# con-bot-j2-1.net
KiCad netlist of a schematic drawn in Altium Designer
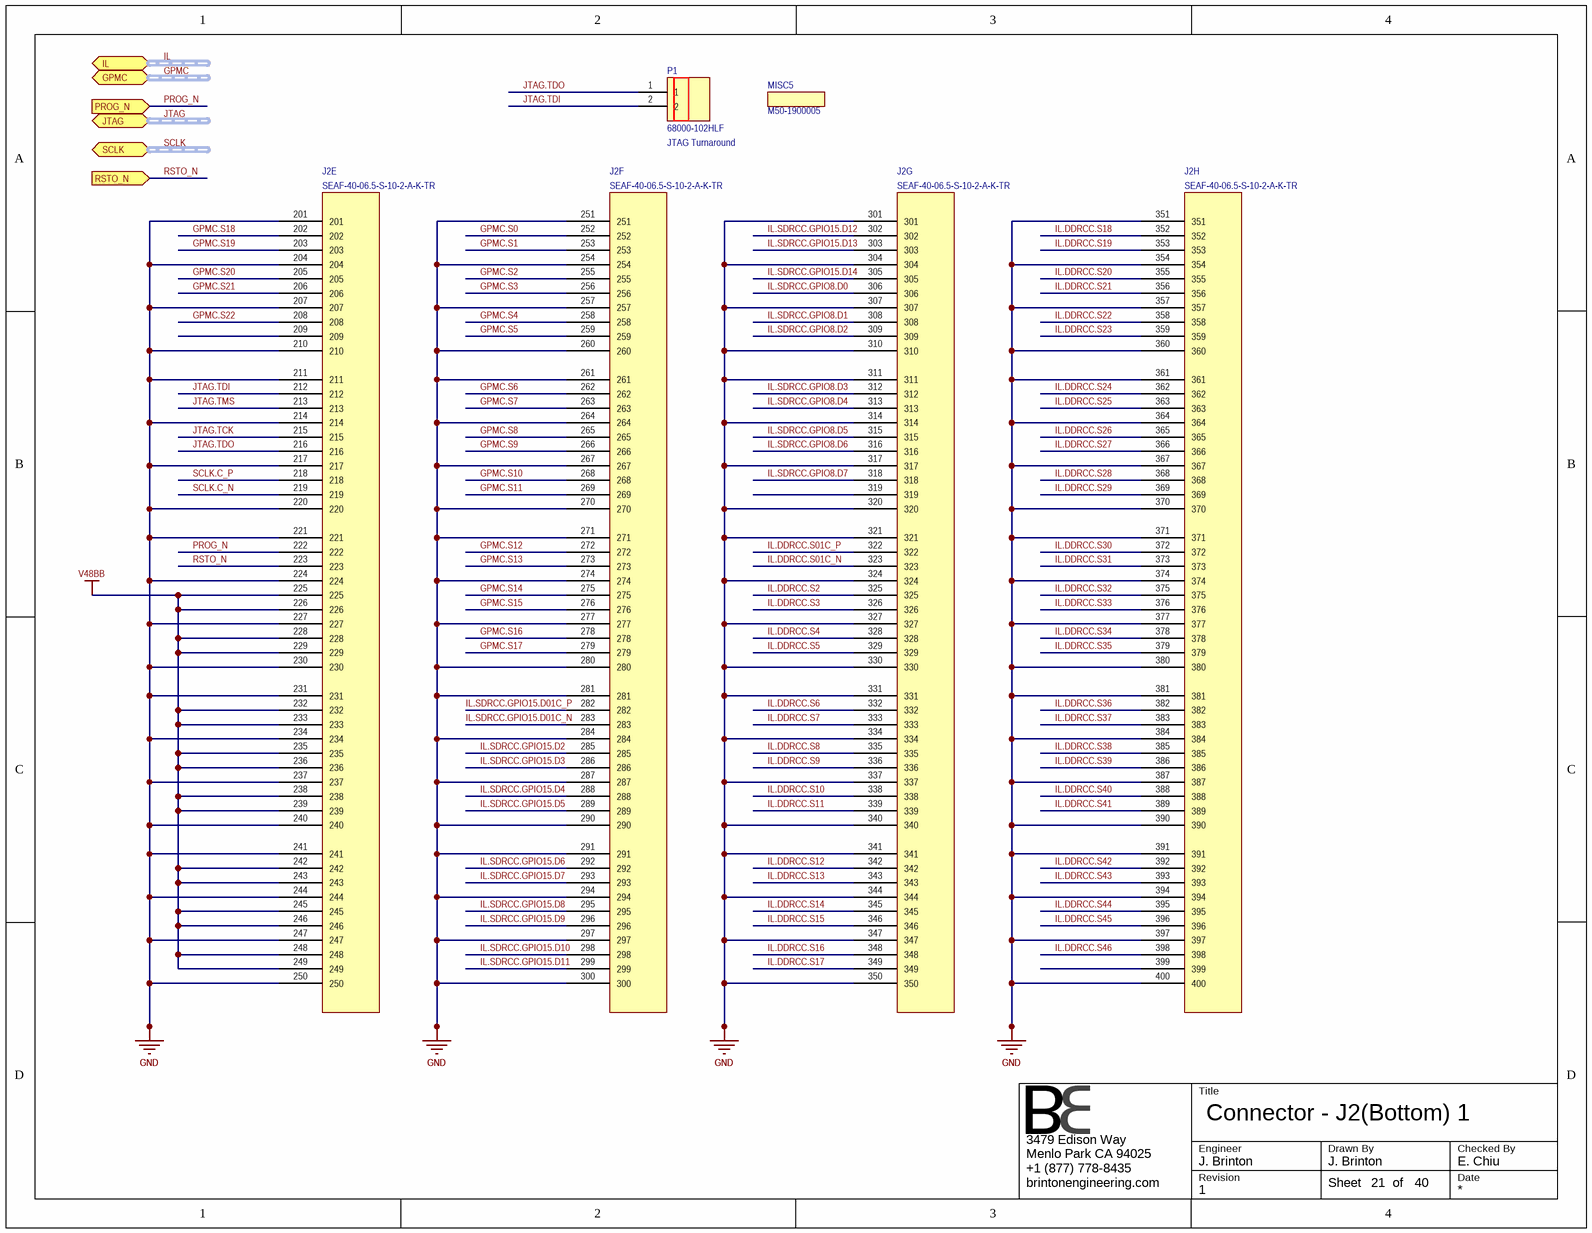
[diagram p0: con-bot-j2-1.SchDoc]

(export (version "E")
  (design (tool "Eeschema 10.0.6"))
  (components
    (comp (ref "J2")
      (value "SEAF-40-06.5-S-10-2-A-K-TR")
      (footprint "samtec:SEAF-40-06.5-S-10-2-A-K-TR")
      (description "Terminal Array Assembly, Surface Mount, 0.050\" Pitch, 400 Pins")
      (fields (field (name "MANUFACTURER") "Samtec"))
      (libsource (lib "samtec") (part "SEAF-40-06.5-S-10-2-A-K-TR"))
    )
    (comp (ref "MISC5")
      (value "M50-1900005")
      (description "1.27mm Jumper Socket")
      (fields (field (name "MANUFACTURER") "Harwin"))
      (libsource (lib "harwin") (part "M50-1900005"))
    )
    (comp (ref "P1")
      (value "68000-102HLF")
      (footprint "68000-102HLF")
      (description "Connector; Header; 2 Position; 0.1\" Pitch")
      (fields (field (name "MANUFACTURER") "FCI"))
      (libsource (lib "fci") (part "68000-102HLF"))
    )
  )
  (nets
    (net (code "5") (name "/GPMC.S0") (class "Default")
      (node (ref "J2") (pin "252") (pinfunction "252_252") (pintype "passive"))
    )
    (net (code "6") (name "/GPMC.S1") (class "Default")
      (node (ref "J2") (pin "253") (pinfunction "253_253") (pintype "passive"))
    )
    (net (code "7") (name "/GPMC.S2") (class "Default")
      (node (ref "J2") (pin "255") (pinfunction "255_255") (pintype "passive"))
    )
    (net (code "8") (name "/GPMC.S3") (class "Default")
      (node (ref "J2") (pin "256") (pinfunction "256_256") (pintype "passive"))
    )
    (net (code "9") (name "/GPMC.S4") (class "Default")
      (node (ref "J2") (pin "258") (pinfunction "258_258") (pintype "passive"))
    )
    (net (code "10") (name "/GPMC.S5") (class "Default")
      (node (ref "J2") (pin "259") (pinfunction "259_259") (pintype "passive"))
    )
    (net (code "11") (name "/GPMC.S6") (class "Default")
      (node (ref "J2") (pin "262") (pinfunction "262_262") (pintype "passive"))
    )
    (net (code "12") (name "/GPMC.S7") (class "Default")
      (node (ref "J2") (pin "263") (pinfunction "263_263") (pintype "passive"))
    )
    (net (code "13") (name "/GPMC.S8") (class "Default")
      (node (ref "J2") (pin "265") (pinfunction "265_265") (pintype "passive"))
    )
    (net (code "14") (name "/GPMC.S9") (class "Default")
      (node (ref "J2") (pin "266") (pinfunction "266_266") (pintype "passive"))
    )
    (net (code "15") (name "/GPMC.S10") (class "Default")
      (node (ref "J2") (pin "268") (pinfunction "268_268") (pintype "passive"))
    )
    (net (code "16") (name "/GPMC.S11") (class "Default")
      (node (ref "J2") (pin "269") (pinfunction "269_269") (pintype "passive"))
    )
    (net (code "17") (name "/GPMC.S12") (class "Default")
      (node (ref "J2") (pin "272") (pinfunction "272_272") (pintype "passive"))
    )
    (net (code "18") (name "/GPMC.S13") (class "Default")
      (node (ref "J2") (pin "273") (pinfunction "273_273") (pintype "passive"))
    )
    (net (code "19") (name "/GPMC.S14") (class "Default")
      (node (ref "J2") (pin "275") (pinfunction "275_275") (pintype "passive"))
    )
    (net (code "20") (name "/GPMC.S15") (class "Default")
      (node (ref "J2") (pin "276") (pinfunction "276_276") (pintype "passive"))
    )
    (net (code "21") (name "/GPMC.S16") (class "Default")
      (node (ref "J2") (pin "278") (pinfunction "278_278") (pintype "passive"))
    )
    (net (code "22") (name "/GPMC.S17") (class "Default")
      (node (ref "J2") (pin "279") (pinfunction "279_279") (pintype "passive"))
    )
    (net (code "23") (name "/GPMC.S18") (class "Default")
      (node (ref "J2") (pin "202") (pinfunction "202_202") (pintype "passive"))
    )
    (net (code "24") (name "/GPMC.S19") (class "Default")
      (node (ref "J2") (pin "203") (pinfunction "203_203") (pintype "passive"))
    )
    (net (code "25") (name "/GPMC.S20") (class "Default")
      (node (ref "J2") (pin "205") (pinfunction "205_205") (pintype "passive"))
    )
    (net (code "26") (name "/GPMC.S21") (class "Default")
      (node (ref "J2") (pin "206") (pinfunction "206_206") (pintype "passive"))
    )
    (net (code "27") (name "/GPMC.S22") (class "Default")
      (node (ref "J2") (pin "208") (pinfunction "208_208") (pintype "passive"))
    )
    (net (code "28") (name "/IL.DDRCC.S01C_N") (class "Default")
      (node (ref "J2") (pin "323") (pinfunction "323_323") (pintype "passive"))
    )
    (net (code "29") (name "/IL.DDRCC.S01C_P") (class "Default")
      (node (ref "J2") (pin "322") (pinfunction "322_322") (pintype "passive"))
    )
    (net (code "30") (name "/IL.DDRCC.S2") (class "Default")
      (node (ref "J2") (pin "325") (pinfunction "325_325") (pintype "passive"))
    )
    (net (code "31") (name "/IL.DDRCC.S3") (class "Default")
      (node (ref "J2") (pin "326") (pinfunction "326_326") (pintype "passive"))
    )
    (net (code "32") (name "/IL.DDRCC.S4") (class "Default")
      (node (ref "J2") (pin "328") (pinfunction "328_328") (pintype "passive"))
    )
    (net (code "33") (name "/IL.DDRCC.S5") (class "Default")
      (node (ref "J2") (pin "329") (pinfunction "329_329") (pintype "passive"))
    )
    (net (code "34") (name "/IL.DDRCC.S6") (class "Default")
      (node (ref "J2") (pin "332") (pinfunction "332_332") (pintype "passive"))
    )
    (net (code "35") (name "/IL.DDRCC.S7") (class "Default")
      (node (ref "J2") (pin "333") (pinfunction "333_333") (pintype "passive"))
    )
    (net (code "36") (name "/IL.DDRCC.S8") (class "Default")
      (node (ref "J2") (pin "335") (pinfunction "335_335") (pintype "passive"))
    )
    (net (code "37") (name "/IL.DDRCC.S9") (class "Default")
      (node (ref "J2") (pin "336") (pinfunction "336_336") (pintype "passive"))
    )
    (net (code "38") (name "/IL.DDRCC.S10") (class "Default")
      (node (ref "J2") (pin "338") (pinfunction "338_338") (pintype "passive"))
    )
    (net (code "39") (name "/IL.DDRCC.S11") (class "Default")
      (node (ref "J2") (pin "339") (pinfunction "339_339") (pintype "passive"))
    )
    (net (code "40") (name "/IL.DDRCC.S12") (class "Default")
      (node (ref "J2") (pin "342") (pinfunction "342_342") (pintype "passive"))
    )
    (net (code "41") (name "/IL.DDRCC.S13") (class "Default")
      (node (ref "J2") (pin "343") (pinfunction "343_343") (pintype "passive"))
    )
    (net (code "42") (name "/IL.DDRCC.S14") (class "Default")
      (node (ref "J2") (pin "345") (pinfunction "345_345") (pintype "passive"))
    )
    (net (code "43") (name "/IL.DDRCC.S15") (class "Default")
      (node (ref "J2") (pin "346") (pinfunction "346_346") (pintype "passive"))
    )
    (net (code "44") (name "/IL.DDRCC.S16") (class "Default")
      (node (ref "J2") (pin "348") (pinfunction "348_348") (pintype "passive"))
    )
    (net (code "45") (name "/IL.DDRCC.S17") (class "Default")
      (node (ref "J2") (pin "349") (pinfunction "349_349") (pintype "passive"))
    )
    (net (code "46") (name "/IL.DDRCC.S18") (class "Default")
      (node (ref "J2") (pin "352") (pinfunction "352_352") (pintype "passive"))
    )
    (net (code "47") (name "/IL.DDRCC.S19") (class "Default")
      (node (ref "J2") (pin "353") (pinfunction "353_353") (pintype "passive"))
    )
    (net (code "48") (name "/IL.DDRCC.S20") (class "Default")
      (node (ref "J2") (pin "355") (pinfunction "355_355") (pintype "passive"))
    )
    (net (code "49") (name "/IL.DDRCC.S21") (class "Default")
      (node (ref "J2") (pin "356") (pinfunction "356_356") (pintype "passive"))
    )
    (net (code "50") (name "/IL.DDRCC.S22") (class "Default")
      (node (ref "J2") (pin "358") (pinfunction "358_358") (pintype "passive"))
    )
    (net (code "51") (name "/IL.DDRCC.S23") (class "Default")
      (node (ref "J2") (pin "359") (pinfunction "359_359") (pintype "passive"))
    )
    (net (code "52") (name "/IL.DDRCC.S24") (class "Default")
      (node (ref "J2") (pin "362") (pinfunction "362_362") (pintype "passive"))
    )
    (net (code "53") (name "/IL.DDRCC.S25") (class "Default")
      (node (ref "J2") (pin "363") (pinfunction "363_363") (pintype "passive"))
    )
    (net (code "54") (name "/IL.DDRCC.S26") (class "Default")
      (node (ref "J2") (pin "365") (pinfunction "365_365") (pintype "passive"))
    )
    (net (code "55") (name "/IL.DDRCC.S27") (class "Default")
      (node (ref "J2") (pin "366") (pinfunction "366_366") (pintype "passive"))
    )
    (net (code "56") (name "/IL.DDRCC.S28") (class "Default")
      (node (ref "J2") (pin "368") (pinfunction "368_368") (pintype "passive"))
    )
    (net (code "57") (name "/IL.DDRCC.S29") (class "Default")
      (node (ref "J2") (pin "369") (pinfunction "369_369") (pintype "passive"))
    )
    (net (code "58") (name "/IL.DDRCC.S30") (class "Default")
      (node (ref "J2") (pin "372") (pinfunction "372_372") (pintype "passive"))
    )
    (net (code "59") (name "/IL.DDRCC.S31") (class "Default")
      (node (ref "J2") (pin "373") (pinfunction "373_373") (pintype "passive"))
    )
    (net (code "60") (name "/IL.DDRCC.S32") (class "Default")
      (node (ref "J2") (pin "375") (pinfunction "375_375") (pintype "passive"))
    )
    (net (code "61") (name "/IL.DDRCC.S33") (class "Default")
      (node (ref "J2") (pin "376") (pinfunction "376_376") (pintype "passive"))
    )
    (net (code "62") (name "/IL.DDRCC.S34") (class "Default")
      (node (ref "J2") (pin "378") (pinfunction "378_378") (pintype "passive"))
    )
    (net (code "63") (name "/IL.DDRCC.S35") (class "Default")
      (node (ref "J2") (pin "379") (pinfunction "379_379") (pintype "passive"))
    )
    (net (code "64") (name "/IL.DDRCC.S36") (class "Default")
      (node (ref "J2") (pin "382") (pinfunction "382_382") (pintype "passive"))
    )
    (net (code "65") (name "/IL.DDRCC.S37") (class "Default")
      (node (ref "J2") (pin "383") (pinfunction "383_383") (pintype "passive"))
    )
    (net (code "66") (name "/IL.DDRCC.S38") (class "Default")
      (node (ref "J2") (pin "385") (pinfunction "385_385") (pintype "passive"))
    )
    (net (code "67") (name "/IL.DDRCC.S39") (class "Default")
      (node (ref "J2") (pin "386") (pinfunction "386_386") (pintype "passive"))
    )
    (net (code "68") (name "/IL.DDRCC.S40") (class "Default")
      (node (ref "J2") (pin "388") (pinfunction "388_388") (pintype "passive"))
    )
    (net (code "69") (name "/IL.DDRCC.S41") (class "Default")
      (node (ref "J2") (pin "389") (pinfunction "389_389") (pintype "passive"))
    )
    (net (code "70") (name "/IL.DDRCC.S42") (class "Default")
      (node (ref "J2") (pin "392") (pinfunction "392_392") (pintype "passive"))
    )
    (net (code "71") (name "/IL.DDRCC.S43") (class "Default")
      (node (ref "J2") (pin "393") (pinfunction "393_393") (pintype "passive"))
    )
    (net (code "72") (name "/IL.DDRCC.S44") (class "Default")
      (node (ref "J2") (pin "395") (pinfunction "395_395") (pintype "passive"))
    )
    (net (code "73") (name "/IL.DDRCC.S45") (class "Default")
      (node (ref "J2") (pin "396") (pinfunction "396_396") (pintype "passive"))
    )
    (net (code "74") (name "/IL.DDRCC.S46") (class "Default")
      (node (ref "J2") (pin "398") (pinfunction "398_398") (pintype "passive"))
    )
    (net (code "75") (name "/IL.SDRCC.GPIO8.D0") (class "Default")
      (node (ref "J2") (pin "306") (pinfunction "306_306") (pintype "passive"))
    )
    (net (code "76") (name "/IL.SDRCC.GPIO8.D1") (class "Default")
      (node (ref "J2") (pin "308") (pinfunction "308_308") (pintype "passive"))
    )
    (net (code "77") (name "/IL.SDRCC.GPIO8.D2") (class "Default")
      (node (ref "J2") (pin "309") (pinfunction "309_309") (pintype "passive"))
    )
    (net (code "78") (name "/IL.SDRCC.GPIO8.D3") (class "Default")
      (node (ref "J2") (pin "312") (pinfunction "312_312") (pintype "passive"))
    )
    (net (code "79") (name "/IL.SDRCC.GPIO8.D4") (class "Default")
      (node (ref "J2") (pin "313") (pinfunction "313_313") (pintype "passive"))
    )
    (net (code "80") (name "/IL.SDRCC.GPIO8.D5") (class "Default")
      (node (ref "J2") (pin "315") (pinfunction "315_315") (pintype "passive"))
    )
    (net (code "81") (name "/IL.SDRCC.GPIO8.D6") (class "Default")
      (node (ref "J2") (pin "316") (pinfunction "316_316") (pintype "passive"))
    )
    (net (code "82") (name "/IL.SDRCC.GPIO8.D7") (class "Default")
      (node (ref "J2") (pin "318") (pinfunction "318_318") (pintype "passive"))
    )
    (net (code "83") (name "/IL.SDRCC.GPIO15.D01C_N") (class "Default")
      (node (ref "J2") (pin "283") (pinfunction "283_283") (pintype "passive"))
    )
    (net (code "84") (name "/IL.SDRCC.GPIO15.D01C_P") (class "Default")
      (node (ref "J2") (pin "282") (pinfunction "282_282") (pintype "passive"))
    )
    (net (code "85") (name "/IL.SDRCC.GPIO15.D2") (class "Default")
      (node (ref "J2") (pin "285") (pinfunction "285_285") (pintype "passive"))
    )
    (net (code "86") (name "/IL.SDRCC.GPIO15.D3") (class "Default")
      (node (ref "J2") (pin "286") (pinfunction "286_286") (pintype "passive"))
    )
    (net (code "87") (name "/IL.SDRCC.GPIO15.D4") (class "Default")
      (node (ref "J2") (pin "288") (pinfunction "288_288") (pintype "passive"))
    )
    (net (code "88") (name "/IL.SDRCC.GPIO15.D5") (class "Default")
      (node (ref "J2") (pin "289") (pinfunction "289_289") (pintype "passive"))
    )
    (net (code "89") (name "/IL.SDRCC.GPIO15.D6") (class "Default")
      (node (ref "J2") (pin "292") (pinfunction "292_292") (pintype "passive"))
    )
    (net (code "90") (name "/IL.SDRCC.GPIO15.D7") (class "Default")
      (node (ref "J2") (pin "293") (pinfunction "293_293") (pintype "passive"))
    )
    (net (code "91") (name "/IL.SDRCC.GPIO15.D8") (class "Default")
      (node (ref "J2") (pin "295") (pinfunction "295_295") (pintype "passive"))
    )
    (net (code "92") (name "/IL.SDRCC.GPIO15.D9") (class "Default")
      (node (ref "J2") (pin "296") (pinfunction "296_296") (pintype "passive"))
    )
    (net (code "93") (name "/IL.SDRCC.GPIO15.D10") (class "Default")
      (node (ref "J2") (pin "298") (pinfunction "298_298") (pintype "passive"))
    )
    (net (code "94") (name "/IL.SDRCC.GPIO15.D11") (class "Default")
      (node (ref "J2") (pin "299") (pinfunction "299_299") (pintype "passive"))
    )
    (net (code "95") (name "/IL.SDRCC.GPIO15.D12") (class "Default")
      (node (ref "J2") (pin "302") (pinfunction "302_302") (pintype "passive"))
    )
    (net (code "96") (name "/IL.SDRCC.GPIO15.D13") (class "Default")
      (node (ref "J2") (pin "303") (pinfunction "303_303") (pintype "passive"))
    )
    (net (code "97") (name "/IL.SDRCC.GPIO15.D14") (class "Default")
      (node (ref "J2") (pin "305") (pinfunction "305_305") (pintype "passive"))
    )
    (net (code "98") (name "/JTAG.TCK") (class "Default")
      (node (ref "J2") (pin "215") (pinfunction "215_215") (pintype "passive"))
    )
    (net (code "99") (name "/JTAG.TDI") (class "Default")
      (node (ref "J2") (pin "212") (pinfunction "212_212") (pintype "passive"))
      (node (ref "P1") (pin "2") (pinfunction "2_2") (pintype "passive"))
    )
    (net (code "100") (name "/JTAG.TDO") (class "Default")
      (node (ref "J2") (pin "216") (pinfunction "216_216") (pintype "passive"))
      (node (ref "P1") (pin "1") (pinfunction "1_1") (pintype "passive"))
    )
    (net (code "101") (name "/JTAG.TMS") (class "Default")
      (node (ref "J2") (pin "213") (pinfunction "213_213") (pintype "passive"))
    )
    (net (code "102") (name "/PROG_N") (class "Default")
      (node (ref "J2") (pin "222") (pinfunction "222_222") (pintype "passive"))
    )
    (net (code "103") (name "/RSTO_N") (class "Default")
      (node (ref "J2") (pin "223") (pinfunction "223_223") (pintype "passive"))
    )
    (net (code "104") (name "/SCLK.C_N") (class "Default")
      (node (ref "J2") (pin "219") (pinfunction "219_219") (pintype "passive"))
    )
    (net (code "105") (name "/SCLK.C_P") (class "Default")
      (node (ref "J2") (pin "218") (pinfunction "218_218") (pintype "passive"))
    )
    (net (code "110") (name "GND") (class "Default")
      (node (ref "J2") (pin "201") (pinfunction "201_201") (pintype "passive"))
      (node (ref "J2") (pin "204") (pinfunction "204_204") (pintype "passive"))
      (node (ref "J2") (pin "207") (pinfunction "207_207") (pintype "passive"))
      (node (ref "J2") (pin "210") (pinfunction "210_210") (pintype "passive"))
      (node (ref "J2") (pin "211") (pinfunction "211_211") (pintype "passive"))
      (node (ref "J2") (pin "214") (pinfunction "214_214") (pintype "passive"))
      (node (ref "J2") (pin "217") (pinfunction "217_217") (pintype "passive"))
      (node (ref "J2") (pin "220") (pinfunction "220_220") (pintype "passive"))
      (node (ref "J2") (pin "221") (pinfunction "221_221") (pintype "passive"))
      (node (ref "J2") (pin "224") (pinfunction "224_224") (pintype "passive"))
      (node (ref "J2") (pin "227") (pinfunction "227_227") (pintype "passive"))
      (node (ref "J2") (pin "230") (pinfunction "230_230") (pintype "passive"))
      (node (ref "J2") (pin "231") (pinfunction "231_231") (pintype "passive"))
      (node (ref "J2") (pin "234") (pinfunction "234_234") (pintype "passive"))
      (node (ref "J2") (pin "237") (pinfunction "237_237") (pintype "passive"))
      (node (ref "J2") (pin "240") (pinfunction "240_240") (pintype "passive"))
      (node (ref "J2") (pin "241") (pinfunction "241_241") (pintype "passive"))
      (node (ref "J2") (pin "244") (pinfunction "244_244") (pintype "passive"))
      (node (ref "J2") (pin "247") (pinfunction "247_247") (pintype "passive"))
      (node (ref "J2") (pin "250") (pinfunction "250_250") (pintype "passive"))
      (node (ref "J2") (pin "251") (pinfunction "251_251") (pintype "passive"))
      (node (ref "J2") (pin "254") (pinfunction "254_254") (pintype "passive"))
      (node (ref "J2") (pin "257") (pinfunction "257_257") (pintype "passive"))
      (node (ref "J2") (pin "260") (pinfunction "260_260") (pintype "passive"))
      (node (ref "J2") (pin "261") (pinfunction "261_261") (pintype "passive"))
      (node (ref "J2") (pin "264") (pinfunction "264_264") (pintype "passive"))
      (node (ref "J2") (pin "267") (pinfunction "267_267") (pintype "passive"))
      (node (ref "J2") (pin "270") (pinfunction "270_270") (pintype "passive"))
      (node (ref "J2") (pin "271") (pinfunction "271_271") (pintype "passive"))
      (node (ref "J2") (pin "274") (pinfunction "274_274") (pintype "passive"))
      (node (ref "J2") (pin "277") (pinfunction "277_277") (pintype "passive"))
      (node (ref "J2") (pin "280") (pinfunction "280_280") (pintype "passive"))
      (node (ref "J2") (pin "281") (pinfunction "281_281") (pintype "passive"))
      (node (ref "J2") (pin "284") (pinfunction "284_284") (pintype "passive"))
      (node (ref "J2") (pin "287") (pinfunction "287_287") (pintype "passive"))
      (node (ref "J2") (pin "290") (pinfunction "290_290") (pintype "passive"))
      (node (ref "J2") (pin "291") (pinfunction "291_291") (pintype "passive"))
      (node (ref "J2") (pin "294") (pinfunction "294_294") (pintype "passive"))
      (node (ref "J2") (pin "297") (pinfunction "297_297") (pintype "passive"))
      (node (ref "J2") (pin "300") (pinfunction "300_300") (pintype "passive"))
      (node (ref "J2") (pin "301") (pinfunction "301_301") (pintype "passive"))
      (node (ref "J2") (pin "304") (pinfunction "304_304") (pintype "passive"))
      (node (ref "J2") (pin "307") (pinfunction "307_307") (pintype "passive"))
      (node (ref "J2") (pin "310") (pinfunction "310_310") (pintype "passive"))
      (node (ref "J2") (pin "311") (pinfunction "311_311") (pintype "passive"))
      (node (ref "J2") (pin "314") (pinfunction "314_314") (pintype "passive"))
      (node (ref "J2") (pin "317") (pinfunction "317_317") (pintype "passive"))
      (node (ref "J2") (pin "320") (pinfunction "320_320") (pintype "passive"))
      (node (ref "J2") (pin "321") (pinfunction "321_321") (pintype "passive"))
      (node (ref "J2") (pin "324") (pinfunction "324_324") (pintype "passive"))
      (node (ref "J2") (pin "327") (pinfunction "327_327") (pintype "passive"))
      (node (ref "J2") (pin "330") (pinfunction "330_330") (pintype "passive"))
      (node (ref "J2") (pin "331") (pinfunction "331_331") (pintype "passive"))
      (node (ref "J2") (pin "334") (pinfunction "334_334") (pintype "passive"))
      (node (ref "J2") (pin "337") (pinfunction "337_337") (pintype "passive"))
      (node (ref "J2") (pin "340") (pinfunction "340_340") (pintype "passive"))
      (node (ref "J2") (pin "341") (pinfunction "341_341") (pintype "passive"))
      (node (ref "J2") (pin "344") (pinfunction "344_344") (pintype "passive"))
      (node (ref "J2") (pin "347") (pinfunction "347_347") (pintype "passive"))
      (node (ref "J2") (pin "350") (pinfunction "350_350") (pintype "passive"))
      (node (ref "J2") (pin "351") (pinfunction "351_351") (pintype "passive"))
      (node (ref "J2") (pin "354") (pinfunction "354_354") (pintype "passive"))
      (node (ref "J2") (pin "357") (pinfunction "357_357") (pintype "passive"))
      (node (ref "J2") (pin "360") (pinfunction "360_360") (pintype "passive"))
      (node (ref "J2") (pin "361") (pinfunction "361_361") (pintype "passive"))
      (node (ref "J2") (pin "364") (pinfunction "364_364") (pintype "passive"))
      (node (ref "J2") (pin "367") (pinfunction "367_367") (pintype "passive"))
      (node (ref "J2") (pin "370") (pinfunction "370_370") (pintype "passive"))
      (node (ref "J2") (pin "371") (pinfunction "371_371") (pintype "passive"))
      (node (ref "J2") (pin "374") (pinfunction "374_374") (pintype "passive"))
      (node (ref "J2") (pin "377") (pinfunction "377_377") (pintype "passive"))
      (node (ref "J2") (pin "380") (pinfunction "380_380") (pintype "passive"))
      (node (ref "J2") (pin "381") (pinfunction "381_381") (pintype "passive"))
      (node (ref "J2") (pin "384") (pinfunction "384_384") (pintype "passive"))
      (node (ref "J2") (pin "387") (pinfunction "387_387") (pintype "passive"))
      (node (ref "J2") (pin "390") (pinfunction "390_390") (pintype "passive"))
      (node (ref "J2") (pin "391") (pinfunction "391_391") (pintype "passive"))
      (node (ref "J2") (pin "394") (pinfunction "394_394") (pintype "passive"))
      (node (ref "J2") (pin "397") (pinfunction "397_397") (pintype "passive"))
      (node (ref "J2") (pin "400") (pinfunction "400_400") (pintype "passive"))
    )
    (net (code "111") (name "V48BB") (class "Default")
      (node (ref "J2") (pin "225") (pinfunction "225_225") (pintype "passive"))
      (node (ref "J2") (pin "226") (pinfunction "226_226") (pintype "passive"))
      (node (ref "J2") (pin "228") (pinfunction "228_228") (pintype "passive"))
      (node (ref "J2") (pin "229") (pinfunction "229_229") (pintype "passive"))
      (node (ref "J2") (pin "232") (pinfunction "232_232") (pintype "passive"))
      (node (ref "J2") (pin "233") (pinfunction "233_233") (pintype "passive"))
      (node (ref "J2") (pin "235") (pinfunction "235_235") (pintype "passive"))
      (node (ref "J2") (pin "236") (pinfunction "236_236") (pintype "passive"))
      (node (ref "J2") (pin "238") (pinfunction "238_238") (pintype "passive"))
      (node (ref "J2") (pin "239") (pinfunction "239_239") (pintype "passive"))
      (node (ref "J2") (pin "242") (pinfunction "242_242") (pintype "passive"))
      (node (ref "J2") (pin "243") (pinfunction "243_243") (pintype "passive"))
      (node (ref "J2") (pin "245") (pinfunction "245_245") (pintype "passive"))
      (node (ref "J2") (pin "246") (pinfunction "246_246") (pintype "passive"))
      (node (ref "J2") (pin "248") (pinfunction "248_248") (pintype "passive"))
      (node (ref "J2") (pin "249") (pinfunction "249_249") (pintype "passive"))
    )
    (net (code "112") (name "unconnected-(J2-Pad209)") (class "Default")
      (node (ref "J2") (pin "209") (pinfunction "209_209") (pintype "passive"))
    )
    (net (code "113") (name "unconnected-(J2-Pad319)") (class "Default")
      (node (ref "J2") (pin "319") (pinfunction "319_319") (pintype "passive"))
    )
    (net (code "114") (name "unconnected-(J2-Pad399)") (class "Default")
      (node (ref "J2") (pin "399") (pinfunction "399_399") (pintype "passive"))
    )
  )
)
